# schematic.net
KiCad netlist of a schematic drawn in EAGLE
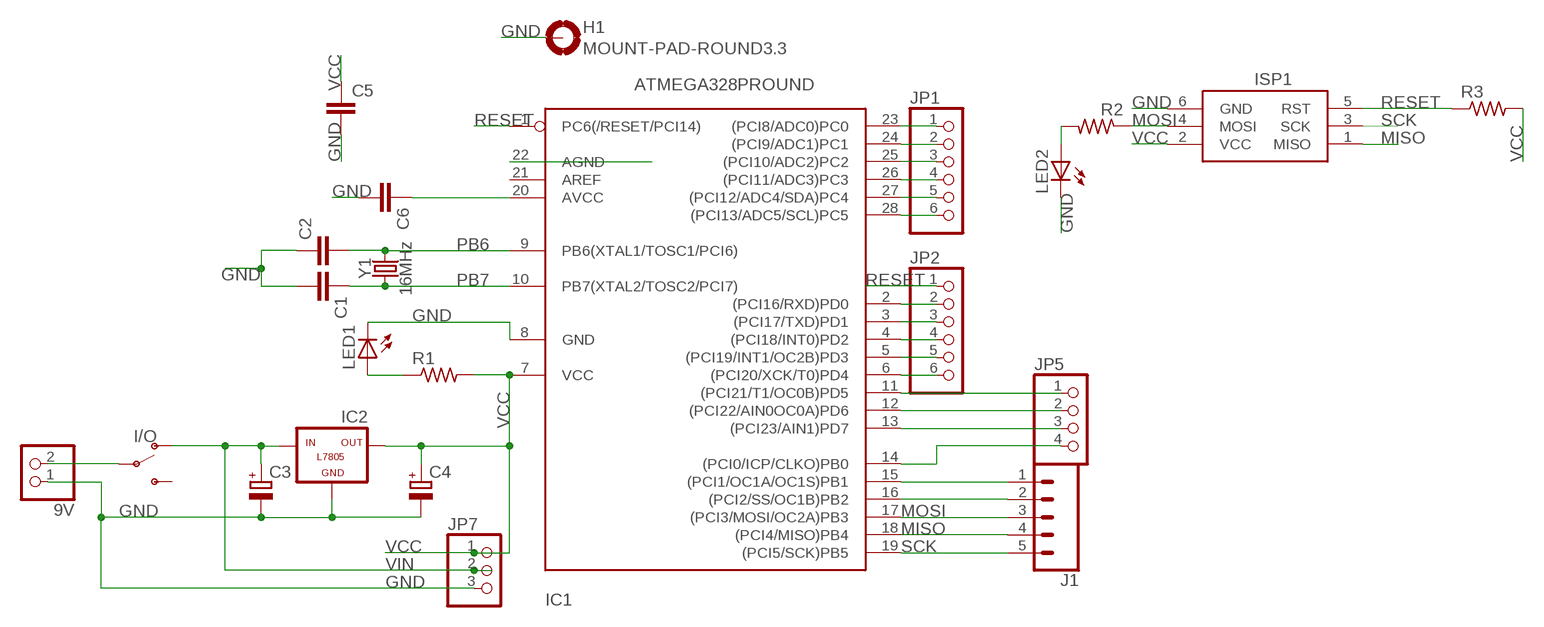
[diagram p0: schematic, sheet 1]

(export (version "E")
  (design (tool "Eeschema 10.0.6"))
  (components
    (comp (ref "9V")
      (value "PINHD-1X2M")
      (footprint "eagle-import:1X02M")
      (libsource (lib "eagle-import") (part "PINHD-1X2M"))
    )
    (comp (ref "C1")
      (value "C5/5")
      (footprint "eagle-import:C5B5")
      (libsource (lib "eagle-import") (part "C5/5"))
    )
    (comp (ref "C2")
      (value "C5/5")
      (footprint "eagle-import:C5B5")
      (libsource (lib "eagle-import") (part "C5/5"))
    )
    (comp (ref "C3")
      (value "CPOL-EUB45181A")
      (footprint "eagle-import:B45181A")
      (libsource (lib "eagle-import") (part "CPOL-EUB45181A"))
    )
    (comp (ref "C4")
      (value "CPOL-EUB45181A")
      (footprint "eagle-import:B45181A")
      (libsource (lib "eagle-import") (part "CPOL-EUB45181A"))
    )
    (comp (ref "C5")
      (value "C-EU025-025X050")
      (footprint "eagle-import:C025-025X050")
      (libsource (lib "eagle-import") (part "C-EU025-025X050"))
    )
    (comp (ref "C6")
      (value "C-EU025-025X050")
      (footprint "eagle-import:C025-025X050")
      (libsource (lib "eagle-import") (part "C-EU025-025X050"))
    )
    (comp (ref "H1")
      (value "MOUNT-PAD-ROUND3.3")
      (footprint "eagle-import:3,3-PAD")
      (libsource (lib "eagle-import") (part "MOUNT-PAD-ROUND3.3"))
    )
    (comp (ref "I/O")
      (value "SWITCH-SPDT-PTH-11.6X4.0MM")
      (footprint "eagle-import:SWITCH_SPDT_PTH_11.6X4.0MM")
      (libsource (lib "eagle-import") (part "SWITCH-SPDT-PTH-11.6X4.0MM"))
    )
    (comp (ref "IC1")
      (value "ATMEGA328PROUND")
      (footprint "eagle-import:DIL28-3-ROUND")
      (libsource (lib "eagle-import") (part "ATMEGA328PROUND"))
    )
    (comp (ref "IC2")
      (value "L7805")
      (footprint "eagle-import:78XXL")
      (libsource (lib "eagle-import") (part "L7805"))
    )
    (comp (ref "ISP1")
      (value "AVRISP-6")
      (footprint "eagle-import:AVRISP")
      (libsource (lib "eagle-import") (part "AVRISP-6"))
    )
    (comp (ref "J1")
      (value "CONN_05")
      (footprint "eagle-import:1X05")
      (libsource (lib "eagle-import") (part "CONN_05"))
    )
    (comp (ref "JP1")
      (value "PINHD-1X6")
      (footprint "eagle-import:1X06")
      (libsource (lib "eagle-import") (part "PINHD-1X6"))
    )
    (comp (ref "JP2")
      (value "PINHD-1X6")
      (footprint "eagle-import:1X06")
      (libsource (lib "eagle-import") (part "PINHD-1X6"))
    )
    (comp (ref "JP5")
      (value "PINHD-1X4")
      (footprint "eagle-import:1X04")
      (libsource (lib "eagle-import") (part "PINHD-1X4"))
    )
    (comp (ref "JP7")
      (value "PINHD-1X3")
      (footprint "eagle-import:1X03")
      (libsource (lib "eagle-import") (part "PINHD-1X3"))
    )
    (comp (ref "LED1")
      (value "LED3MM")
      (footprint "eagle-import:LED3MM")
      (libsource (lib "eagle-import") (part "LED3MM"))
    )
    (comp (ref "LED2")
      (value "LED3MM")
      (footprint "eagle-import:LED3MM")
      (libsource (lib "eagle-import") (part "LED3MM"))
    )
    (comp (ref "R1")
      (value "R-US_0207/10")
      (footprint "eagle-import:0207_10")
      (libsource (lib "eagle-import") (part "R-US_0207/10"))
    )
    (comp (ref "R2")
      (value "R-US_0207/10")
      (footprint "eagle-import:0207_10")
      (libsource (lib "eagle-import") (part "R-US_0207/10"))
    )
    (comp (ref "R3")
      (value "R-US_0207/10")
      (footprint "eagle-import:0207_10")
      (libsource (lib "eagle-import") (part "R-US_0207/10"))
    )
    (comp (ref "Y1")
      (value "16MHz")
      (footprint "eagle-import:HC49US")
      (libsource (lib "eagle-import") (part "CRYSTAL-16MHZPTH-HC49US"))
    )
  )
  (nets
    (net (code "1") (name "/GND") (class "Default")
      (node (ref "9V") (pin "1") (pinfunction "1_1") (pintype "passive"))
      (node (ref "C1") (pin "2") (pinfunction "2_2") (pintype "passive"))
      (node (ref "C2") (pin "1") (pinfunction "1_1") (pintype "passive"))
      (node (ref "C3") (pin "-") (pinfunction "-_-") (pintype "passive"))
      (node (ref "C4") (pin "-") (pinfunction "-_-") (pintype "passive"))
      (node (ref "C5") (pin "2") (pinfunction "2_2") (pintype "passive"))
      (node (ref "C6") (pin "2") (pinfunction "2_2") (pintype "passive"))
      (node (ref "H1") (pin "B3,3") (pinfunction "MOUNT_B3,3") (pintype "passive"))
      (node (ref "IC1") (pin "22") (pinfunction "AGND_22") (pintype "bidirectional"))
      (node (ref "IC1") (pin "8") (pinfunction "GND_8") (pintype "bidirectional"))
      (node (ref "IC2") (pin "GND") (pinfunction "GND_GND") (pintype "input"))
      (node (ref "ISP1") (pin "6") (pinfunction "GND_6") (pintype "power_in"))
      (node (ref "JP7") (pin "3") (pinfunction "3_3") (pintype "passive"))
      (node (ref "LED1") (pin "K") (pinfunction "C_K") (pintype "passive"))
      (node (ref "LED2") (pin "K") (pinfunction "C_K") (pintype "passive"))
    )
    (net (code "2") (name "/MISO") (class "Default")
      (node (ref "IC1") (pin "18") (pinfunction "(PCI4/MISO)PB4_18") (pintype "bidirectional"))
      (node (ref "ISP1") (pin "1") (pinfunction "MISO_1") (pintype "input"))
      (node (ref "J1") (pin "4") (pinfunction "4_4") (pintype "passive"))
    )
    (net (code "3") (name "/MOSI") (class "Default")
      (node (ref "IC1") (pin "17") (pinfunction "(PCI3/MOSI/OC2A)PB3_17") (pintype "bidirectional"))
      (node (ref "ISP1") (pin "4") (pinfunction "MOSI_4") (pintype "output"))
      (node (ref "J1") (pin "3") (pinfunction "3_3") (pintype "passive"))
      (node (ref "R2") (pin "1") (pinfunction "1_1") (pintype "passive"))
    )
    (net (code "4") (name "/PB6") (class "Default")
      (node (ref "C2") (pin "2") (pinfunction "2_2") (pintype "passive"))
      (node (ref "IC1") (pin "9") (pinfunction "PB6(XTAL1/TOSC1/PCI6)_9") (pintype "bidirectional"))
      (node (ref "Y1") (pin "2") (pinfunction "2_2") (pintype "passive"))
    )
    (net (code "5") (name "/PB7") (class "Default")
      (node (ref "C1") (pin "1") (pinfunction "1_1") (pintype "passive"))
      (node (ref "IC1") (pin "10") (pinfunction "PB7(XTAL2/TOSC2/PCI7)_10") (pintype "bidirectional"))
      (node (ref "Y1") (pin "1") (pinfunction "1_1") (pintype "passive"))
    )
    (net (code "6") (name "/RESET") (class "Default")
      (node (ref "IC1") (pin "1") (pinfunction "PC6(/RESET/PCI14)_1") (pintype "bidirectional"))
      (node (ref "ISP1") (pin "5") (pinfunction "RST_5") (pintype "output"))
      (node (ref "JP2") (pin "1") (pinfunction "1_1") (pintype "passive"))
      (node (ref "R3") (pin "1") (pinfunction "1_1") (pintype "passive"))
    )
    (net (code "7") (name "/SCK") (class "Default")
      (node (ref "IC1") (pin "19") (pinfunction "(PCI5/SCK)PB5_19") (pintype "bidirectional"))
      (node (ref "ISP1") (pin "3") (pinfunction "SCK_3") (pintype "output"))
      (node (ref "J1") (pin "5") (pinfunction "5_5") (pintype "passive"))
    )
    (net (code "8") (name "/VCC") (class "Default")
      (node (ref "C4") (pin "+") (pinfunction "+_+") (pintype "passive"))
      (node (ref "C5") (pin "1") (pinfunction "1_1") (pintype "passive"))
      (node (ref "IC1") (pin "7") (pinfunction "VCC_7") (pintype "bidirectional"))
      (node (ref "IC2") (pin "OUT") (pinfunction "OUT_OUT") (pintype "passive"))
      (node (ref "ISP1") (pin "2") (pinfunction "VCC_2") (pintype "power_in"))
      (node (ref "JP7") (pin "1") (pinfunction "1_1") (pintype "passive"))
      (node (ref "R1") (pin "2") (pinfunction "2_2") (pintype "passive"))
      (node (ref "R3") (pin "2") (pinfunction "2_2") (pintype "passive"))
    )
    (net (code "9") (name "/VIN") (class "Default")
      (node (ref "C3") (pin "+") (pinfunction "+_+") (pintype "passive"))
      (node (ref "I/O") (pin "1") (pinfunction "O_1") (pintype "passive"))
      (node (ref "IC2") (pin "IN") (pinfunction "IN_IN") (pintype "input"))
      (node (ref "JP7") (pin "2") (pinfunction "2_2") (pintype "passive"))
    )
    (net (code "10") (name "Net-(I/O-P)") (class "Default")
      (node (ref "9V") (pin "2") (pinfunction "2_2") (pintype "passive"))
      (node (ref "I/O") (pin "2") (pinfunction "P_2") (pintype "passive"))
    )
    (net (code "11") (name "Net-(IC1-(PCI0{slash}ICP{slash}CLKO)PB0)") (class "Default")
      (node (ref "IC1") (pin "14") (pinfunction "(PCI0/ICP/CLKO)PB0_14") (pintype "bidirectional"))
      (node (ref "JP5") (pin "4") (pinfunction "4_4") (pintype "passive"))
    )
    (net (code "12") (name "Net-(IC1-(PCI1{slash}OC1A{slash}OC1S)PB1)") (class "Default")
      (node (ref "IC1") (pin "15") (pinfunction "(PCI1/OC1A/OC1S)PB1_15") (pintype "bidirectional"))
      (node (ref "J1") (pin "1") (pinfunction "1_1") (pintype "passive"))
    )
    (net (code "13") (name "Net-(IC1-(PCI2{slash}SS{slash}OC1B)PB2)") (class "Default")
      (node (ref "IC1") (pin "16") (pinfunction "(PCI2/SS/OC1B)PB2_16") (pintype "bidirectional"))
      (node (ref "J1") (pin "2") (pinfunction "2_2") (pintype "passive"))
    )
    (net (code "14") (name "Net-(IC1-(PCI8{slash}ADC0)PC0)") (class "Default")
      (node (ref "IC1") (pin "23") (pinfunction "(PCI8/ADC0)PC0_23") (pintype "bidirectional"))
      (node (ref "JP1") (pin "1") (pinfunction "1_1") (pintype "passive"))
    )
    (net (code "15") (name "Net-(IC1-(PCI9{slash}ADC1)PC1)") (class "Default")
      (node (ref "IC1") (pin "24") (pinfunction "(PCI9/ADC1)PC1_24") (pintype "bidirectional"))
      (node (ref "JP1") (pin "2") (pinfunction "2_2") (pintype "passive"))
    )
    (net (code "16") (name "Net-(IC1-(PCI10{slash}ADC2)PC2)") (class "Default")
      (node (ref "IC1") (pin "25") (pinfunction "(PCI10/ADC2)PC2_25") (pintype "bidirectional"))
      (node (ref "JP1") (pin "3") (pinfunction "3_3") (pintype "passive"))
    )
    (net (code "17") (name "Net-(IC1-(PCI11{slash}ADC3)PC3)") (class "Default")
      (node (ref "IC1") (pin "26") (pinfunction "(PCI11/ADC3)PC3_26") (pintype "bidirectional"))
      (node (ref "JP1") (pin "4") (pinfunction "4_4") (pintype "passive"))
    )
    (net (code "18") (name "Net-(IC1-(PCI12{slash}ADC4{slash}SDA)PC4)") (class "Default")
      (node (ref "IC1") (pin "27") (pinfunction "(PCI12/ADC4/SDA)PC4_27") (pintype "bidirectional"))
      (node (ref "JP1") (pin "5") (pinfunction "5_5") (pintype "passive"))
    )
    (net (code "19") (name "Net-(IC1-(PCI13{slash}ADC5{slash}SCL)PC5)") (class "Default")
      (node (ref "IC1") (pin "28") (pinfunction "(PCI13/ADC5/SCL)PC5_28") (pintype "bidirectional"))
      (node (ref "JP1") (pin "6") (pinfunction "6_6") (pintype "passive"))
    )
    (net (code "20") (name "Net-(IC1-(PCI16{slash}RXD)PD0)") (class "Default")
      (node (ref "IC1") (pin "2") (pinfunction "(PCI16/RXD)PD0_2") (pintype "bidirectional"))
      (node (ref "JP2") (pin "2") (pinfunction "2_2") (pintype "passive"))
    )
    (net (code "21") (name "Net-(IC1-(PCI17{slash}TXD)PD1)") (class "Default")
      (node (ref "IC1") (pin "3") (pinfunction "(PCI17/TXD)PD1_3") (pintype "bidirectional"))
      (node (ref "JP2") (pin "3") (pinfunction "3_3") (pintype "passive"))
    )
    (net (code "22") (name "Net-(IC1-(PCI18{slash}INT0)PD2)") (class "Default")
      (node (ref "IC1") (pin "4") (pinfunction "(PCI18/INT0)PD2_4") (pintype "bidirectional"))
      (node (ref "JP2") (pin "4") (pinfunction "4_4") (pintype "passive"))
    )
    (net (code "23") (name "Net-(IC1-(PCI19{slash}INT1{slash}OC2B)PD3)") (class "Default")
      (node (ref "IC1") (pin "5") (pinfunction "(PCI19/INT1/OC2B)PD3_5") (pintype "bidirectional"))
      (node (ref "JP2") (pin "5") (pinfunction "5_5") (pintype "passive"))
    )
    (net (code "24") (name "Net-(IC1-(PCI20{slash}XCK{slash}T0)PD4)") (class "Default")
      (node (ref "IC1") (pin "6") (pinfunction "(PCI20/XCK/T0)PD4_6") (pintype "bidirectional"))
      (node (ref "JP2") (pin "6") (pinfunction "6_6") (pintype "passive"))
    )
    (net (code "25") (name "Net-(IC1-(PCI21{slash}T1{slash}OC0B)PD5)") (class "Default")
      (node (ref "IC1") (pin "11") (pinfunction "(PCI21/T1/OC0B)PD5_11") (pintype "bidirectional"))
      (node (ref "JP5") (pin "1") (pinfunction "1_1") (pintype "passive"))
    )
    (net (code "26") (name "Net-(IC1-(PCI22{slash}AIN0OC0A)PD6)") (class "Default")
      (node (ref "IC1") (pin "12") (pinfunction "(PCI22/AIN0OC0A)PD6_12") (pintype "bidirectional"))
      (node (ref "JP5") (pin "2") (pinfunction "2_2") (pintype "passive"))
    )
    (net (code "27") (name "Net-(IC1-(PCI23{slash}AIN1)PD7)") (class "Default")
      (node (ref "IC1") (pin "13") (pinfunction "(PCI23/AIN1)PD7_13") (pintype "bidirectional"))
      (node (ref "JP5") (pin "3") (pinfunction "3_3") (pintype "passive"))
    )
    (net (code "28") (name "Net-(IC1-AVCC)") (class "Default")
      (node (ref "C6") (pin "1") (pinfunction "1_1") (pintype "passive"))
      (node (ref "IC1") (pin "20") (pinfunction "AVCC_20") (pintype "bidirectional"))
    )
    (net (code "29") (name "Net-(LED1-PadA)") (class "Default")
      (node (ref "LED1") (pin "A") (pinfunction "A_A") (pintype "passive"))
      (node (ref "R1") (pin "1") (pinfunction "1_1") (pintype "passive"))
    )
    (net (code "30") (name "Net-(LED2-PadA)") (class "Default")
      (node (ref "LED2") (pin "A") (pinfunction "A_A") (pintype "passive"))
      (node (ref "R2") (pin "2") (pinfunction "2_2") (pintype "passive"))
    )
    (net (code "31") (name "unconnected-(I/O-S-Pad3)") (class "Default")
      (node (ref "I/O") (pin "3") (pinfunction "S_3") (pintype "passive"))
    )
    (net (code "32") (name "unconnected-(IC1-AREF-Pad21)") (class "Default")
      (node (ref "IC1") (pin "21") (pinfunction "AREF_21") (pintype "bidirectional"))
    )
  )
)
